# relays_board_v1_0.net
KiCad netlist of a schematic drawn in EAGLE
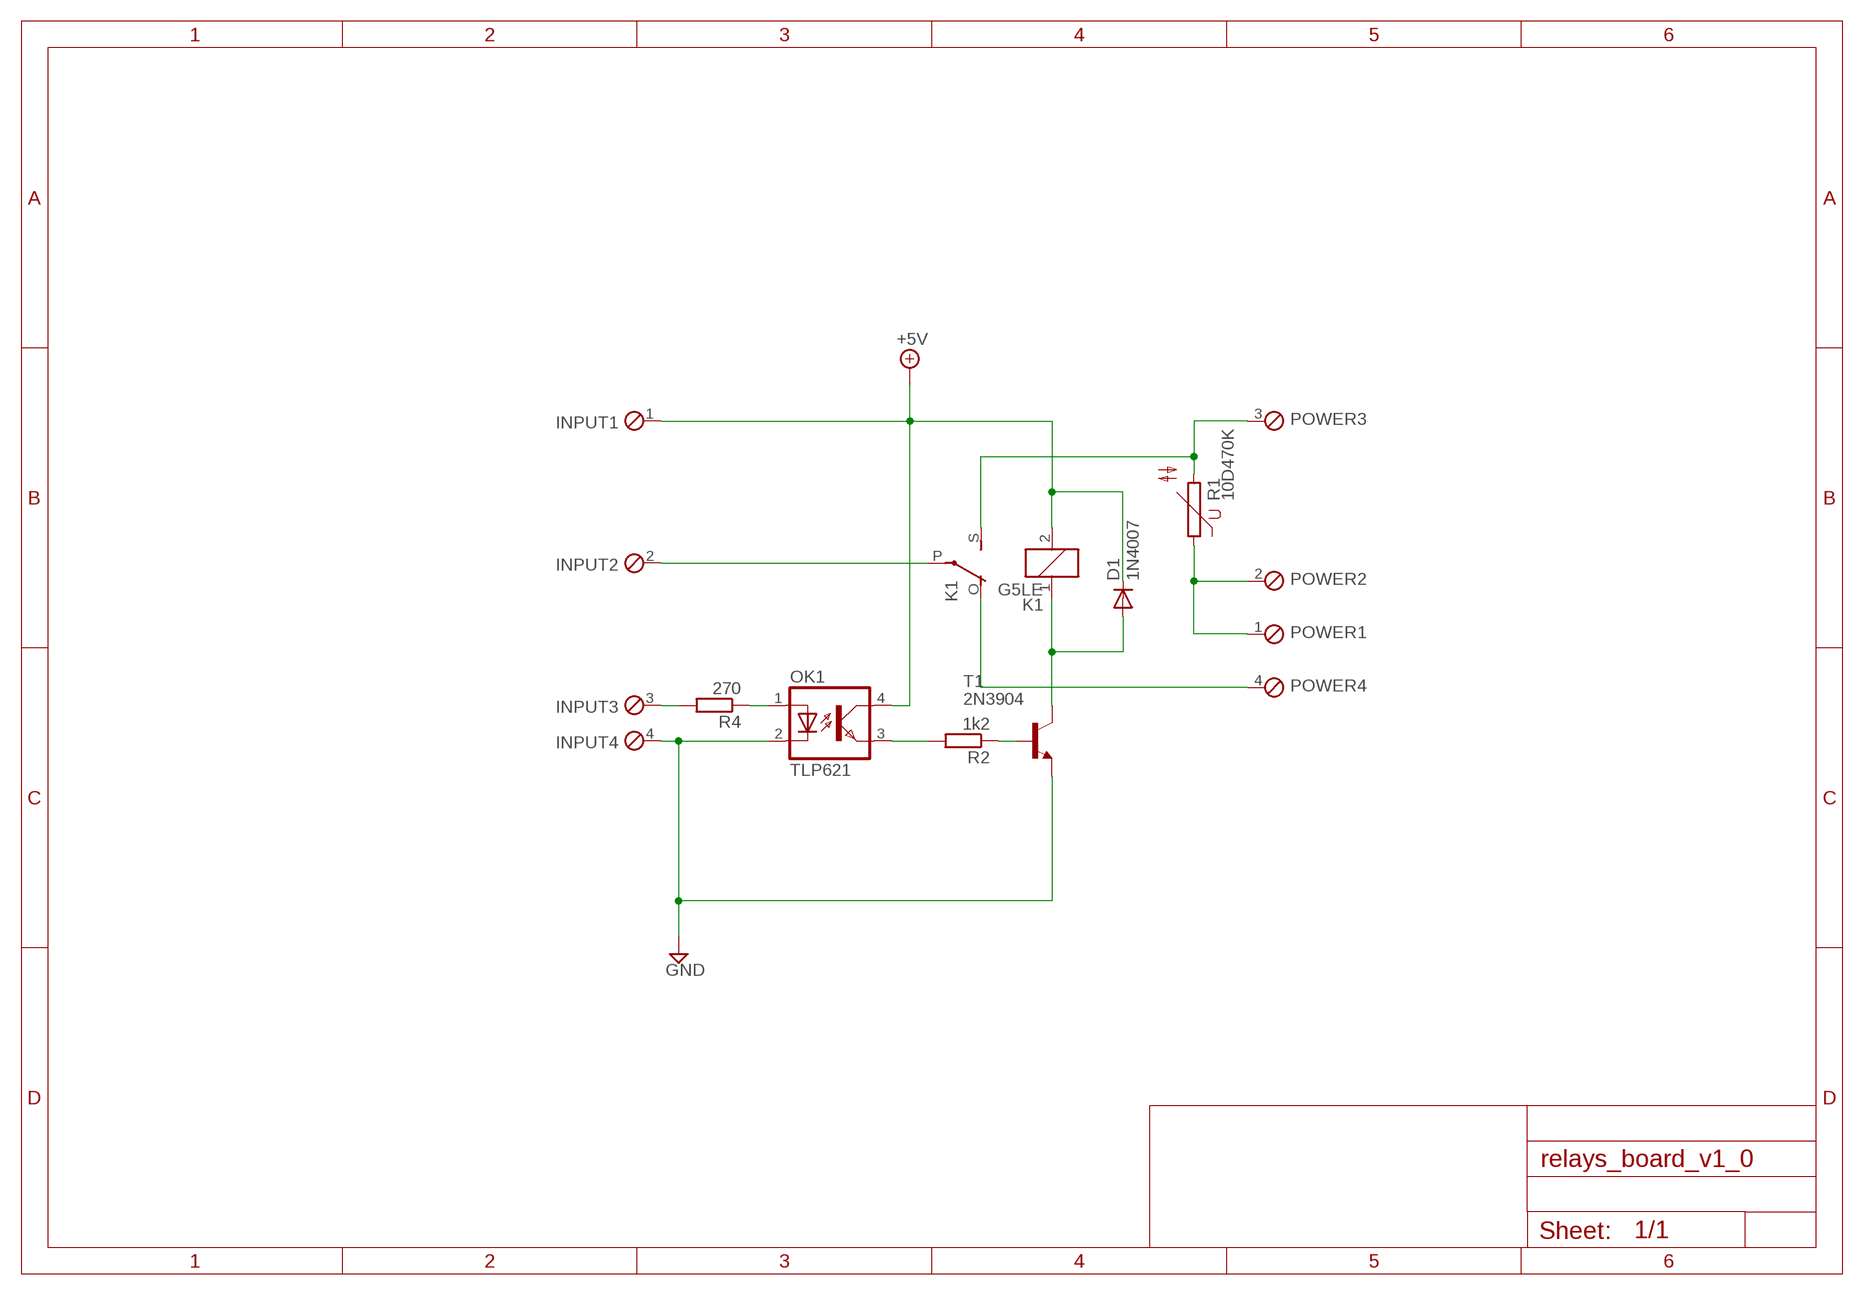
[diagram p0: schematic, sheet 1]

(export (version "E")
  (design (tool "Eeschema 10.0.6"))
  (components
    (comp (ref "D1")
      (value "1N4007")
      (footprint "eagle-import:DO41-10")
      (libsource (lib "eagle-import") (part "1N4007"))
    )
    (comp (ref "INPUT")
      (value "OSTTA040161")
      (footprint "eagle-import:040161")
      (libsource (lib "eagle-import") (part "OSTTA040161"))
    )
    (comp (ref "K1")
      (value "G5LE")
      (footprint "eagle-import:G5LE")
      (libsource (lib "eagle-import") (part "G5LE"))
    )
    (comp (ref "OK1")
      (value "TLP621")
      (footprint "eagle-import:DIL04")
      (libsource (lib "eagle-import") (part "TLP621"))
    )
    (comp (ref "POWER")
      (value "OSTTA040161")
      (footprint "eagle-import:040161")
      (libsource (lib "eagle-import") (part "OSTTA040161"))
    )
    (comp (ref "R1")
      (value "10D470K")
      (footprint "eagle-import:10D470K")
      (libsource (lib "eagle-import") (part "10D470K"))
    )
    (comp (ref "R2")
      (value "1k2")
      (footprint "eagle-import:0204_7")
      (libsource (lib "eagle-import") (part "R-EU_0204/7"))
    )
    (comp (ref "R4")
      (value "270")
      (footprint "eagle-import:0204_7")
      (libsource (lib "eagle-import") (part "R-EU_0204/7"))
    )
    (comp (ref "T1")
      (value "2N3904")
      (footprint "eagle-import:TO92")
      (libsource (lib "eagle-import") (part "2N3904"))
    )
  )
  (nets
    (net (code "1") (name "+5V") (class "Default")
      (node (ref "D1") (pin "C") (pinfunction "C_C") (pintype "passive"))
      (node (ref "INPUT") (pin "1") (pinfunction "1_1") (pintype "passive"))
      (node (ref "K1") (pin "2") (pinfunction "2_2") (pintype "passive"))
      (node (ref "OK1") (pin "4") (pinfunction "COL_4") (pintype "passive"))
    )
    (net (code "2") (name "GND") (class "Default")
      (node (ref "INPUT") (pin "4") (pinfunction "1_4") (pintype "passive"))
      (node (ref "OK1") (pin "2") (pinfunction "C_2") (pintype "passive"))
      (node (ref "T1") (pin "3") (pinfunction "E_3") (pintype "passive"))
    )
    (net (code "3") (name "Net-(INPUTB-1)") (class "Default")
      (node (ref "INPUT") (pin "2") (pinfunction "1_2") (pintype "passive"))
      (node (ref "K1") (pin "P") (pinfunction "P_P") (pintype "passive"))
    )
    (net (code "4") (name "Net-(INPUTC-1)") (class "Default")
      (node (ref "INPUT") (pin "3") (pinfunction "1_3") (pintype "passive"))
      (node (ref "R4") (pin "2") (pinfunction "2_2") (pintype "passive"))
    )
    (net (code "5") (name "Net-(OK1-A)") (class "Default")
      (node (ref "OK1") (pin "1") (pinfunction "A_1") (pintype "passive"))
      (node (ref "R4") (pin "1") (pinfunction "1_1") (pintype "passive"))
    )
    (net (code "6") (name "Net-(OK1-EMIT)") (class "Default")
      (node (ref "OK1") (pin "3") (pinfunction "EMIT_3") (pintype "passive"))
      (node (ref "R2") (pin "2") (pinfunction "2_2") (pintype "passive"))
    )
    (net (code "7") (name "Net-(POWERB-1)") (class "Default")
      (node (ref "POWER") (pin "1") (pinfunction "1_1") (pintype "passive"))
      (node (ref "POWER") (pin "2") (pinfunction "1_2") (pintype "passive"))
      (node (ref "R1") (pin "1") (pinfunction "1_1") (pintype "passive"))
    )
    (net (code "8") (name "Net-(POWERC-1)") (class "Default")
      (node (ref "K1") (pin "S") (pinfunction "S_S") (pintype "passive"))
      (node (ref "POWER") (pin "3") (pinfunction "1_3") (pintype "passive"))
      (node (ref "R1") (pin "2") (pinfunction "2_2") (pintype "passive"))
    )
    (net (code "9") (name "Net-(POWERD-1)") (class "Default")
      (node (ref "K1") (pin "O") (pinfunction "O_O") (pintype "passive"))
      (node (ref "POWER") (pin "4") (pinfunction "1_4") (pintype "passive"))
    )
    (net (code "10") (name "Net-(T1-B)") (class "Default")
      (node (ref "R2") (pin "1") (pinfunction "1_1") (pintype "passive"))
      (node (ref "T1") (pin "2") (pinfunction "B_2") (pintype "passive"))
    )
    (net (code "11") (name "Net-(T1-C)") (class "Default")
      (node (ref "D1") (pin "A") (pinfunction "A_A") (pintype "passive"))
      (node (ref "K1") (pin "1") (pinfunction "1_1") (pintype "passive"))
      (node (ref "T1") (pin "1") (pinfunction "C_1") (pintype "passive"))
    )
  )
)
